# ProProject_new1_2024-06-04.net
KiCad netlist of a schematic drawn in EasyEDA Pro
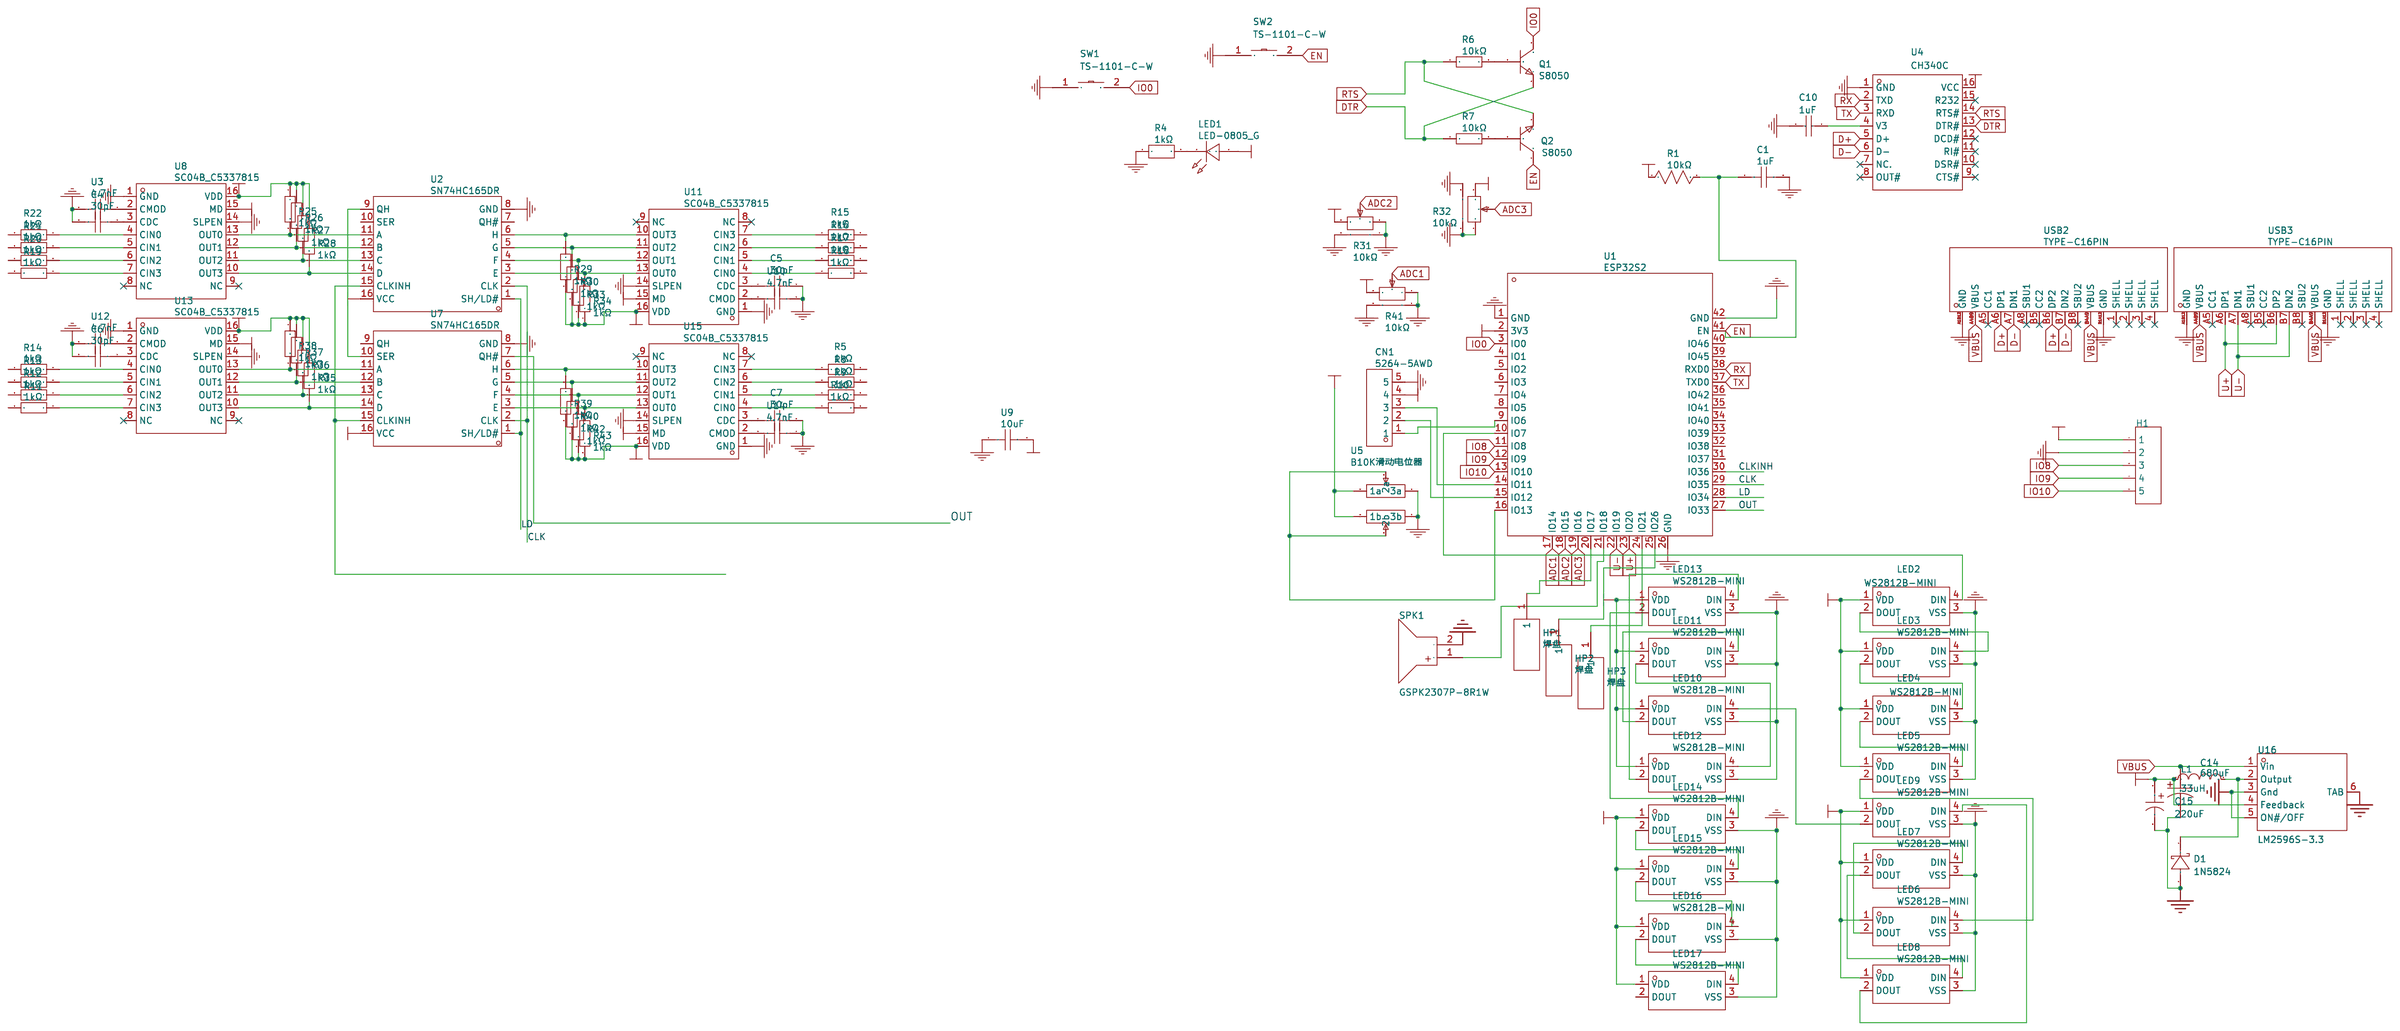
[diagram p0: schematic sheet]

(export (version "E")
  (design (tool "Eeschema 10.0.6"))
  (components
    (comp (ref "C1")
      (value "1uF")
      (footprint "easyedapro:C0603")
      (fields
        (field (name "Manufacturer Part") "CL10A105KB8NNNC")
        (field (name "Manufacturer") "SAMSUNG(三星)")
      )
      (libsource (lib "easyedapro") (part "1u"))
    )
    (comp (ref "C4")
      (value "30pF")
      (footprint "easyedapro:C0603")
      (fields
        (field (name "Manufacturer Part") "TCC0603COG300J500CT")
        (field (name "Manufacturer") "CCTC(三环)")
      )
      (libsource (lib "easyedapro") (part "30pF"))
    )
    (comp (ref "C5")
      (value "30pF")
      (footprint "easyedapro:C0603")
      (fields
        (field (name "Manufacturer Part") "TCC0603COG300J500CT")
        (field (name "Manufacturer") "CCTC(三环)")
      )
      (libsource (lib "easyedapro") (part "30pF"))
    )
    (comp (ref "C6")
      (value "30pF")
      (footprint "easyedapro:C0603")
      (fields
        (field (name "Manufacturer Part") "TCC0603COG300J500CT")
        (field (name "Manufacturer") "CCTC(三环)")
      )
      (libsource (lib "easyedapro") (part "30pF"))
    )
    (comp (ref "C7")
      (value "30pF")
      (footprint "easyedapro:C0603")
      (fields
        (field (name "Manufacturer Part") "TCC0603COG300J500CT")
        (field (name "Manufacturer") "CCTC(三环)")
      )
      (libsource (lib "easyedapro") (part "30pF"))
    )
    (comp (ref "C10")
      (value "1uF")
      (footprint "easyedapro:C0805")
      (fields
        (field (name "Manufacturer Part") "GRM21BR61E226ME44L")
        (field (name "Manufacturer") "muRata(村田)")
      )
      (libsource (lib "easyedapro") (part "1uF"))
    )
    (comp (ref "C14")
      (value "680uF")
      (footprint "easyedapro:CAP-TH_BD6.3-P2.50-D1.0-FD")
      (description "容值:680uF;精度:±20%;额定电压:10V;纹波电流:980mA@100kHz;等效串联电阻:50mΩ@300kHz;")
      (fields
        (field (name "Manufacturer Part") "SHW680UF10V6.3X11")
        (field (name "Manufacturer") "KNSCHA(科尼盛)")
      )
      (libsource (lib "easyedapro") (part "SHW680UF10V6.3X11"))
    )
    (comp (ref "C15")
      (value "220uF")
      (footprint "easyedapro:CAP-TH_BD8.0-P3.50-D0.6-FD-2")
      (description "容值:220uF;精度:±20%;额定电压:35V;纹波电流:1.7A@100kHz;等效串联电阻:40mΩ@100kHz;")
      (fields
        (field (name "Manufacturer Part") "KNH2220UF35V149EC0049")
        (field (name "Manufacturer") "KNSCHA(科尼盛)")
      )
      (libsource (lib "easyedapro") (part "KNH2220UF35V149EC0049"))
    )
    (comp (ref "CN1")
      (value "5264-5AWD")
      (footprint "easyedapro:CONN-TH_5P-P2.50_5264-5AWD")
      (fields (field (name "Manufacturer Part") "5264-5AWD米色") (field (name "Manufacturer") "BOOMELE(博穆精密)"))
      (libsource (lib "easyedapro") (part "5264-5AWD"))
    )
    (comp (ref "D1")
      (value "1N5824")
      (footprint "easyedapro:DO-27_BD5.3-L8.4-P12.40-D1.3-RD")
      (description "二极管配置:独立式;正向压降(Vf):550mV@5A;直流反向耐压(Vr):30V;平均整流电流(Io):5A;")
      (fields (field (name "Manufacturer") "FUXINSEMI(富芯森美)"))
      (libsource (lib "easyedapro") (part "1N5824_C7503125"))
    )
    (comp (ref "H1")
      (value "~")
      (footprint "easyedapro:HDR-TH_5P-P2.54-V-F")
      (libsource (lib "easyedapro") (part "Header-Female-2.54_1x5"))
    )
    (comp (ref "HP1")
      (value "焊盘")
      (footprint "easyedapro:焊盘")
      (fields (field (name "Manufacturer Part") "....."))
      (libsource (lib "easyedapro") (part "焊盘"))
    )
    (comp (ref "HP2")
      (value "焊盘")
      (footprint "easyedapro:焊盘")
      (fields (field (name "Manufacturer Part") "....."))
      (libsource (lib "easyedapro") (part "焊盘"))
    )
    (comp (ref "HP3")
      (value "焊盘")
      (footprint "easyedapro:焊盘")
      (fields (field (name "Manufacturer Part") "....."))
      (libsource (lib "easyedapro") (part "焊盘"))
    )
    (comp (ref "L1")
      (value "33uH")
      (footprint "easyedapro:IND-SMD_L7.0-W6.6_FXL0630")
      (description "电感值:33uH;精度:±20%;额定电流:2A;饱和电流(Isat):2.5A;类型:一体成型电感;")
      (fields (field (name "Manufacturer Part") "FXL0630-330-M") (field (name "Manufacturer") "cjiang(长江微电)"))
      (libsource (lib "easyedapro") (part "FXL0630-330-M"))
    )
    (comp (ref "LED1")
      (value "LED-0805_G")
      (footprint "easyedapro:LED0805_GREEN")
      (fields (field (name "Manufacturer Part") "NCD0805G1") (field (name "Manufacturer") "国星光电"))
      (libsource (lib "easyedapro") (part "LED-0805_G"))
    )
    (comp (ref "LED2")
      (value "WS2812B-MINI")
      (footprint "easyedapro:LED-SMD_4P-L3.5-W3.5-TL_WS2812B")
      (fields
        (field (name "Manufacturer Part") "WS2812B-MINI-V3/W")
        (field (name "Manufacturer") "worldsemi")
      )
      (libsource (lib "easyedapro") (part "WS2812B-MINI"))
    )
    (comp (ref "LED3")
      (value "WS2812B-MINI")
      (footprint "easyedapro:LED-SMD_4P-L3.5-W3.5-TL_WS2812B")
      (fields
        (field (name "Manufacturer Part") "WS2812B-MINI-V3/W")
        (field (name "Manufacturer") "worldsemi")
      )
      (libsource (lib "easyedapro") (part "WS2812B-MINI"))
    )
    (comp (ref "LED4")
      (value "WS2812B-MINI")
      (footprint "easyedapro:LED-SMD_4P-L3.5-W3.5-TL_WS2812B")
      (fields
        (field (name "Manufacturer Part") "WS2812B-MINI-V3/W")
        (field (name "Manufacturer") "worldsemi")
      )
      (libsource (lib "easyedapro") (part "WS2812B-MINI"))
    )
    (comp (ref "LED5")
      (value "WS2812B-MINI")
      (footprint "easyedapro:LED-SMD_4P-L3.5-W3.5-TL_WS2812B")
      (fields
        (field (name "Manufacturer Part") "WS2812B-MINI-V3/W")
        (field (name "Manufacturer") "worldsemi")
      )
      (libsource (lib "easyedapro") (part "WS2812B-MINI"))
    )
    (comp (ref "LED6")
      (value "WS2812B-MINI")
      (footprint "easyedapro:LED-SMD_4P-L3.5-W3.5-TL_WS2812B")
      (fields
        (field (name "Manufacturer Part") "WS2812B-MINI-V3/W")
        (field (name "Manufacturer") "worldsemi")
      )
      (libsource (lib "easyedapro") (part "WS2812B-MINI"))
    )
    (comp (ref "LED7")
      (value "WS2812B-MINI")
      (footprint "easyedapro:LED-SMD_4P-L3.5-W3.5-TL_WS2812B")
      (fields
        (field (name "Manufacturer Part") "WS2812B-MINI-V3/W")
        (field (name "Manufacturer") "worldsemi")
      )
      (libsource (lib "easyedapro") (part "WS2812B-MINI"))
    )
    (comp (ref "LED8")
      (value "WS2812B-MINI")
      (footprint "easyedapro:LED-SMD_4P-L3.5-W3.5-TL_WS2812B")
      (fields
        (field (name "Manufacturer Part") "WS2812B-MINI-V3/W")
        (field (name "Manufacturer") "worldsemi")
      )
      (libsource (lib "easyedapro") (part "WS2812B-MINI"))
    )
    (comp (ref "LED9")
      (value "WS2812B-MINI")
      (footprint "easyedapro:LED-SMD_4P-L3.5-W3.5-TL_WS2812B")
      (fields
        (field (name "Manufacturer Part") "WS2812B-MINI-V3/W")
        (field (name "Manufacturer") "worldsemi")
      )
      (libsource (lib "easyedapro") (part "WS2812B-MINI"))
    )
    (comp (ref "LED10")
      (value "WS2812B-MINI")
      (footprint "easyedapro:LED-SMD_4P-L3.5-W3.5-TL_WS2812B")
      (fields
        (field (name "Manufacturer Part") "WS2812B-MINI-V3/W")
        (field (name "Manufacturer") "worldsemi")
      )
      (libsource (lib "easyedapro") (part "WS2812B-MINI"))
    )
    (comp (ref "LED11")
      (value "WS2812B-MINI")
      (footprint "easyedapro:LED-SMD_4P-L3.5-W3.5-TL_WS2812B")
      (fields
        (field (name "Manufacturer Part") "WS2812B-MINI-V3/W")
        (field (name "Manufacturer") "worldsemi")
      )
      (libsource (lib "easyedapro") (part "WS2812B-MINI"))
    )
    (comp (ref "LED12")
      (value "WS2812B-MINI")
      (footprint "easyedapro:LED-SMD_4P-L3.5-W3.5-TL_WS2812B")
      (fields
        (field (name "Manufacturer Part") "WS2812B-MINI-V3/W")
        (field (name "Manufacturer") "worldsemi")
      )
      (libsource (lib "easyedapro") (part "WS2812B-MINI"))
    )
    (comp (ref "LED13")
      (value "WS2812B-MINI")
      (footprint "easyedapro:LED-SMD_4P-L3.5-W3.5-TL_WS2812B")
      (fields
        (field (name "Manufacturer Part") "WS2812B-MINI-V3/W")
        (field (name "Manufacturer") "worldsemi")
      )
      (libsource (lib "easyedapro") (part "WS2812B-MINI"))
    )
    (comp (ref "LED14")
      (value "WS2812B-MINI")
      (footprint "easyedapro:LED-SMD_4P-L3.5-W3.5-TL_WS2812B")
      (fields
        (field (name "Manufacturer Part") "WS2812B-MINI-V3/W")
        (field (name "Manufacturer") "worldsemi")
      )
      (libsource (lib "easyedapro") (part "WS2812B-MINI"))
    )
    (comp (ref "LED15")
      (value "WS2812B-MINI")
      (footprint "easyedapro:LED-SMD_4P-L3.5-W3.5-TL_WS2812B")
      (fields
        (field (name "Manufacturer Part") "WS2812B-MINI-V3/W")
        (field (name "Manufacturer") "worldsemi")
      )
      (libsource (lib "easyedapro") (part "WS2812B-MINI"))
    )
    (comp (ref "LED16")
      (value "WS2812B-MINI")
      (footprint "easyedapro:LED-SMD_4P-L3.5-W3.5-TL_WS2812B")
      (fields
        (field (name "Manufacturer Part") "WS2812B-MINI-V3/W")
        (field (name "Manufacturer") "worldsemi")
      )
      (libsource (lib "easyedapro") (part "WS2812B-MINI"))
    )
    (comp (ref "LED17")
      (value "WS2812B-MINI")
      (footprint "easyedapro:LED-SMD_4P-L3.5-W3.5-TL_WS2812B")
      (fields
        (field (name "Manufacturer Part") "WS2812B-MINI-V3/W")
        (field (name "Manufacturer") "worldsemi")
      )
      (libsource (lib "easyedapro") (part "WS2812B-MINI"))
    )
    (comp (ref "Q1")
      (value "S8050")
      (footprint "easyedapro:SOT-23-3_L2.9-W1.3-P1.90-LS2.4-BR")
      (fields (field (name "Manufacturer") "Yenji"))
      (libsource (lib "easyedapro") (part "S8050"))
    )
    (comp (ref "Q2")
      (value "S8050")
      (footprint "easyedapro:SOT-23-3_L2.9-W1.3-P1.90-LS2.4-BR")
      (fields (field (name "Manufacturer") "Yenji"))
      (libsource (lib "") (part "S8050_1"))
    )
    (comp (ref "R1")
      (value "10kΩ")
      (footprint "easyedapro:R0603")
      (fields
        (field (name "Manufacturer Part") "0603WAF1002T5E")
        (field (name "Manufacturer") "UNI-ROYAL(厚声)")
      )
      (libsource (lib "easyedapro") (part "10k"))
    )
    (comp (ref "R4")
      (value "1kΩ")
      (footprint "easyedapro:R0805")
      (fields
        (field (name "Manufacturer Part") "0805W8D1001T5E")
        (field (name "Manufacturer") "UNI-ROYAL(厚声)")
      )
      (libsource (lib "easyedapro") (part "1kΩ"))
    )
    (comp (ref "R5")
      (value "1kΩ")
      (footprint "easyedapro:R0603")
      (fields (field (name "Manufacturer Part") "ERJ3RBD1001V") (field (name "Manufacturer") "PANASONIC(松下)"))
      (libsource (lib "") (part "1kΩ_1"))
    )
    (comp (ref "R6")
      (value "10kΩ")
      (footprint "easyedapro:R0805")
      (fields
        (field (name "Manufacturer Part") "0805W8F1002T5E")
        (field (name "Manufacturer") "UNI-ROYAL(厚声)")
      )
      (libsource (lib "") (part "10kΩ_1"))
    )
    (comp (ref "R7")
      (value "10kΩ")
      (footprint "easyedapro:R0805")
      (fields
        (field (name "Manufacturer Part") "0805W8F1002T5E")
        (field (name "Manufacturer") "UNI-ROYAL(厚声)")
      )
      (libsource (lib "") (part "10kΩ_1"))
    )
    (comp (ref "R8")
      (value "1kΩ")
      (footprint "easyedapro:R0603")
      (fields (field (name "Manufacturer Part") "ERJ3RBD1001V") (field (name "Manufacturer") "PANASONIC(松下)"))
      (libsource (lib "") (part "1kΩ_1"))
    )
    (comp (ref "R9")
      (value "1kΩ")
      (footprint "easyedapro:R0603")
      (fields (field (name "Manufacturer Part") "ERJ3RBD1001V") (field (name "Manufacturer") "PANASONIC(松下)"))
      (libsource (lib "") (part "1kΩ_1"))
    )
    (comp (ref "R10")
      (value "1kΩ")
      (footprint "easyedapro:R0603")
      (fields (field (name "Manufacturer Part") "ERJ3RBD1001V") (field (name "Manufacturer") "PANASONIC(松下)"))
      (libsource (lib "") (part "1kΩ_1"))
    )
    (comp (ref "R11")
      (value "1kΩ")
      (footprint "easyedapro:R0603")
      (fields (field (name "Manufacturer Part") "ERJ3RBD1001V") (field (name "Manufacturer") "PANASONIC(松下)"))
      (libsource (lib "") (part "1kΩ_1"))
    )
    (comp (ref "R12")
      (value "1kΩ")
      (footprint "easyedapro:R0603")
      (fields (field (name "Manufacturer Part") "ERJ3RBD1001V") (field (name "Manufacturer") "PANASONIC(松下)"))
      (libsource (lib "") (part "1kΩ_1"))
    )
    (comp (ref "R13")
      (value "1kΩ")
      (footprint "easyedapro:R0603")
      (fields (field (name "Manufacturer Part") "ERJ3RBD1001V") (field (name "Manufacturer") "PANASONIC(松下)"))
      (libsource (lib "") (part "1kΩ_1"))
    )
    (comp (ref "R14")
      (value "1kΩ")
      (footprint "easyedapro:R0603")
      (fields (field (name "Manufacturer Part") "ERJ3RBD1001V") (field (name "Manufacturer") "PANASONIC(松下)"))
      (libsource (lib "") (part "1kΩ_1"))
    )
    (comp (ref "R15")
      (value "1kΩ")
      (footprint "easyedapro:R0603")
      (fields (field (name "Manufacturer Part") "ERJ3RBD1001V") (field (name "Manufacturer") "PANASONIC(松下)"))
      (libsource (lib "") (part "1kΩ_1"))
    )
    (comp (ref "R16")
      (value "1kΩ")
      (footprint "easyedapro:R0603")
      (fields (field (name "Manufacturer Part") "ERJ3RBD1001V") (field (name "Manufacturer") "PANASONIC(松下)"))
      (libsource (lib "") (part "1kΩ_1"))
    )
    (comp (ref "R17")
      (value "1kΩ")
      (footprint "easyedapro:R0603")
      (fields (field (name "Manufacturer Part") "ERJ3RBD1001V") (field (name "Manufacturer") "PANASONIC(松下)"))
      (libsource (lib "") (part "1kΩ_1"))
    )
    (comp (ref "R18")
      (value "1kΩ")
      (footprint "easyedapro:R0603")
      (fields (field (name "Manufacturer Part") "ERJ3RBD1001V") (field (name "Manufacturer") "PANASONIC(松下)"))
      (libsource (lib "") (part "1kΩ_1"))
    )
    (comp (ref "R19")
      (value "1kΩ")
      (footprint "easyedapro:R0603")
      (fields (field (name "Manufacturer Part") "ERJ3RBD1001V") (field (name "Manufacturer") "PANASONIC(松下)"))
      (libsource (lib "") (part "1kΩ_1"))
    )
    (comp (ref "R20")
      (value "1kΩ")
      (footprint "easyedapro:R0603")
      (fields (field (name "Manufacturer Part") "ERJ3RBD1001V") (field (name "Manufacturer") "PANASONIC(松下)"))
      (libsource (lib "") (part "1kΩ_1"))
    )
    (comp (ref "R21")
      (value "1kΩ")
      (footprint "easyedapro:R0603")
      (fields (field (name "Manufacturer Part") "ERJ3RBD1001V") (field (name "Manufacturer") "PANASONIC(松下)"))
      (libsource (lib "") (part "1kΩ_1"))
    )
    (comp (ref "R22")
      (value "1kΩ")
      (footprint "easyedapro:R0603")
      (fields (field (name "Manufacturer Part") "ERJ3RBD1001V") (field (name "Manufacturer") "PANASONIC(松下)"))
      (libsource (lib "") (part "1kΩ_1"))
    )
    (comp (ref "R25")
      (value "1kΩ")
      (footprint "easyedapro:R0603")
      (fields (field (name "Manufacturer Part") "ERJ3RBD1001V") (field (name "Manufacturer") "PANASONIC(松下)"))
      (libsource (lib "") (part "1kΩ_1"))
    )
    (comp (ref "R26")
      (value "1kΩ")
      (footprint "easyedapro:R0603")
      (fields (field (name "Manufacturer Part") "ERJ3RBD1001V") (field (name "Manufacturer") "PANASONIC(松下)"))
      (libsource (lib "") (part "1kΩ_1"))
    )
    (comp (ref "R27")
      (value "1kΩ")
      (footprint "easyedapro:R0603")
      (fields (field (name "Manufacturer Part") "ERJ3RBD1001V") (field (name "Manufacturer") "PANASONIC(松下)"))
      (libsource (lib "") (part "1kΩ_1"))
    )
    (comp (ref "R28")
      (value "1kΩ")
      (footprint "easyedapro:R0603")
      (fields (field (name "Manufacturer Part") "ERJ3RBD1001V") (field (name "Manufacturer") "PANASONIC(松下)"))
      (libsource (lib "") (part "1kΩ_1"))
    )
    (comp (ref "R29")
      (value "1kΩ")
      (footprint "easyedapro:R0603")
      (fields (field (name "Manufacturer Part") "ERJ3RBD1001V") (field (name "Manufacturer") "PANASONIC(松下)"))
      (libsource (lib "") (part "1kΩ_1"))
    )
    (comp (ref "R30")
      (value "1kΩ")
      (footprint "easyedapro:R0603")
      (fields (field (name "Manufacturer Part") "ERJ3RBD1001V") (field (name "Manufacturer") "PANASONIC(松下)"))
      (libsource (lib "") (part "1kΩ_1"))
    )
    (comp (ref "R31")
      (value "10kΩ")
      (footprint "easyedapro:RES-ADJ-TH_RK09K1130AJ3")
      (fields
        (field (name "Manufacturer Part") "RK09K1130AP5")
        (field (name "Manufacturer") "ALPSALPINE(阿尔卑斯阿尔派)")
      )
      (libsource (lib "easyedapro") (part "10kΩ"))
    )
    (comp (ref "R32")
      (value "10kΩ")
      (footprint "easyedapro:RES-ADJ-TH_RK09K1130AJ3")
      (fields
        (field (name "Manufacturer Part") "RK09K1130AP5")
        (field (name "Manufacturer") "ALPSALPINE(阿尔卑斯阿尔派)")
      )
      (libsource (lib "easyedapro") (part "10kΩ"))
    )
    (comp (ref "R33")
      (value "1kΩ")
      (footprint "easyedapro:R0603")
      (fields (field (name "Manufacturer Part") "ERJ3RBD1001V") (field (name "Manufacturer") "PANASONIC(松下)"))
      (libsource (lib "") (part "1kΩ_1"))
    )
    (comp (ref "R34")
      (value "1kΩ")
      (footprint "easyedapro:R0603")
      (fields (field (name "Manufacturer Part") "ERJ3RBD1001V") (field (name "Manufacturer") "PANASONIC(松下)"))
      (libsource (lib "") (part "1kΩ_1"))
    )
    (comp (ref "R35")
      (value "1kΩ")
      (footprint "easyedapro:R0603")
      (fields (field (name "Manufacturer Part") "ERJ3RBD1001V") (field (name "Manufacturer") "PANASONIC(松下)"))
      (libsource (lib "") (part "1kΩ_1"))
    )
    (comp (ref "R36")
      (value "1kΩ")
      (footprint "easyedapro:R0603")
      (fields (field (name "Manufacturer Part") "ERJ3RBD1001V") (field (name "Manufacturer") "PANASONIC(松下)"))
      (libsource (lib "") (part "1kΩ_1"))
    )
    (comp (ref "R37")
      (value "1kΩ")
      (footprint "easyedapro:R0603")
      (fields (field (name "Manufacturer Part") "ERJ3RBD1001V") (field (name "Manufacturer") "PANASONIC(松下)"))
      (libsource (lib "") (part "1kΩ_1"))
    )
    (comp (ref "R38")
      (value "1kΩ")
      (footprint "easyedapro:R0603")
      (fields (field (name "Manufacturer Part") "ERJ3RBD1001V") (field (name "Manufacturer") "PANASONIC(松下)"))
      (libsource (lib "") (part "1kΩ_1"))
    )
    (comp (ref "R39")
      (value "1kΩ")
      (footprint "easyedapro:R0603")
      (fields (field (name "Manufacturer Part") "ERJ3RBD1001V") (field (name "Manufacturer") "PANASONIC(松下)"))
      (libsource (lib "") (part "1kΩ_1"))
    )
    (comp (ref "R40")
      (value "1kΩ")
      (footprint "easyedapro:R0603")
      (fields (field (name "Manufacturer Part") "ERJ3RBD1001V") (field (name "Manufacturer") "PANASONIC(松下)"))
      (libsource (lib "") (part "1kΩ_1"))
    )
    (comp (ref "R41")
      (value "10kΩ")
      (footprint "easyedapro:RES-ADJ-TH_RK09K1130AJ3")
      (fields
        (field (name "Manufacturer Part") "RK09K1130AP5")
        (field (name "Manufacturer") "ALPSALPINE(阿尔卑斯阿尔派)")
      )
      (libsource (lib "easyedapro") (part "10kΩ"))
    )
    (comp (ref "R42")
      (value "1kΩ")
      (footprint "easyedapro:R0603")
      (fields (field (name "Manufacturer Part") "ERJ3RBD1001V") (field (name "Manufacturer") "PANASONIC(松下)"))
      (libsource (lib "") (part "1kΩ_1"))
    )
    (comp (ref "R43")
      (value "1kΩ")
      (footprint "easyedapro:R0603")
      (fields (field (name "Manufacturer Part") "ERJ3RBD1001V") (field (name "Manufacturer") "PANASONIC(松下)"))
      (libsource (lib "") (part "1kΩ_1"))
    )
    (comp (ref "SPK1")
      (value "GSPK2307P-8R1W")
      (footprint "easyedapro:SPK-TH_BD23.0-P10.00-D0.8-L-RD")
      (fields (field (name "Manufacturer") "INGHAi(赢海)"))
      (libsource (lib "easyedapro") (part "GSPK2307P-8R1W"))
    )
    (comp (ref "SW1")
      (value "TS-1101-C-W")
      (footprint "easyedapro:SW-SMD_L6.0-W3.3-LS8.0")
      (fields (field (name "Manufacturer") "XKB Connectivity(中国星坤)"))
      (libsource (lib "easyedapro") (part "TS-1101-C-W"))
    )
    (comp (ref "SW2")
      (value "TS-1101-C-W")
      (footprint "easyedapro:SW-SMD_L6.0-W3.3-LS8.0")
      (fields (field (name "Manufacturer") "XKB Connectivity(中国星坤)"))
      (libsource (lib "easyedapro") (part "TS-1101-C-W"))
    )
    (comp (ref "U1")
      (value "ESP32S2")
      (footprint "easyedapro:ESP32S2")
      (fields
        (field (name "Manufacturer Part") "ESP32-S2-WROVER-I-N8R2")
        (field (name "Manufacturer") "ESPRESSIF(乐鑫)")
      )
      (libsource (lib "easyedapro") (part "ESP32S2"))
    )
    (comp (ref "U2")
      (value "SN74HC165DR")
      (footprint "easyedapro:SOP-16_L10.0-W3.9-P1.27-LS6.0-BL")
      (fields (field (name "Manufacturer") "TI(德州仪器)"))
      (libsource (lib "easyedapro") (part "SN74HC165DR"))
    )
    (comp (ref "U3")
      (value "4.7nF")
      (footprint "easyedapro:C0603")
      (fields (field (name "Manufacturer Part") "C1608JB2A472M080AA") (field (name "Manufacturer") "TDK"))
      (libsource (lib "easyedapro") (part "4.7nF"))
    )
    (comp (ref "U4")
      (value "CH340C")
      (footprint "easyedapro:SOP-16_L10.0-W3.9-P1.27-LS6.0-BL")
      (fields (field (name "Manufacturer") "WCH(南京沁恒)"))
      (libsource (lib "easyedapro") (part "CH340C"))
    )
    (comp (ref "U5")
      (value "B10K滑动电位器")
      (footprint "easyedapro:B10K")
      (libsource (lib "easyedapro") (part "B10K滑动电位器"))
    )
    (comp (ref "U7")
      (value "SN74HC165DR")
      (footprint "easyedapro:SOP-16_L10.0-W3.9-P1.27-LS6.0-BL")
      (fields (field (name "Manufacturer") "TI(德州仪器)"))
      (libsource (lib "easyedapro") (part "SN74HC165DR"))
    )
    (comp (ref "U8")
      (value "SC04B_C5337815")
      (footprint "easyedapro:SOP-16_L10.0-W3.9-P1.27-LS6.0-BL")
      (fields (field (name "Manufacturer Part") "SC04B") (field (name "Manufacturer") "icman(晶尊微)"))
      (libsource (lib "easyedapro") (part "SC04B_C5337815"))
    )
    (comp (ref "U9")
      (value "10uF")
      (footprint "easyedapro:C1206")
      (fields
        (field (name "Manufacturer Part") "CS3216Y5V106Z350NRI")
        (field (name "Manufacturer") "SAMWHA(三和)")
      )
      (libsource (lib "easyedapro") (part "10uF"))
    )
    (comp (ref "U10")
      (value "4.7nF")
      (footprint "easyedapro:C0603")
      (fields (field (name "Manufacturer Part") "C1608JB2A472M080AA") (field (name "Manufacturer") "TDK"))
      (libsource (lib "easyedapro") (part "4.7nF"))
    )
    (comp (ref "U11")
      (value "SC04B_C5337815")
      (footprint "easyedapro:SOP-16_L10.0-W3.9-P1.27-LS6.0-BL")
      (fields (field (name "Manufacturer Part") "SC04B") (field (name "Manufacturer") "icman(晶尊微)"))
      (libsource (lib "easyedapro") (part "SC04B_C5337815"))
    )
    (comp (ref "U12")
      (value "4.7nF")
      (footprint "easyedapro:C0603")
      (fields (field (name "Manufacturer Part") "C1608JB2A472M080AA") (field (name "Manufacturer") "TDK"))
      (libsource (lib "easyedapro") (part "4.7nF"))
    )
    (comp (ref "U13")
      (value "SC04B_C5337815")
      (footprint "easyedapro:SOP-16_L10.0-W3.9-P1.27-LS6.0-BL")
      (fields (field (name "Manufacturer Part") "SC04B") (field (name "Manufacturer") "icman(晶尊微)"))
      (libsource (lib "easyedapro") (part "SC04B_C5337815"))
    )
    (comp (ref "U14")
      (value "4.7nF")
      (footprint "easyedapro:C0603")
      (fields (field (name "Manufacturer Part") "C1608JB2A472M080AA") (field (name "Manufacturer") "TDK"))
      (libsource (lib "easyedapro") (part "4.7nF"))
    )
    (comp (ref "U15")
      (value "SC04B_C5337815")
      (footprint "easyedapro:SOP-16_L10.0-W3.9-P1.27-LS6.0-BL")
      (fields (field (name "Manufacturer Part") "SC04B") (field (name "Manufacturer") "icman(晶尊微)"))
      (libsource (lib "easyedapro") (part "SC04B_C5337815"))
    )
    (comp (ref "U16")
      (value "LM2596S-3.3")
      (footprint "easyedapro:TO-263-5_L10.0-W8.4-P1.70-LS15.3-BR")
      (description "功能类型:降压型;输出类型:固定;输入电压:40V;输出电压:3.3V;输出电流(最大值):3A;")
      (fields (field (name "Manufacturer") "UMW(友台半导体)"))
      (libsource (lib "easyedapro") (part "LM2596S-3.3"))
    )
    (comp (ref "USB2")
      (value "TYPE-C16PIN")
      (footprint "easyedapro:USB-C-SMD_TYPE-C16PIN")
      (fields (field (name "Manufacturer") "SHOU HAN(首韩)"))
      (libsource (lib "easyedapro") (part "TYPE-C16PIN"))
    )
    (comp (ref "USB3")
      (value "TYPE-C16PIN")
      (footprint "easyedapro:USB-C-SMD_TYPE-C16PIN")
      (fields (field (name "Manufacturer") "SHOU HAN(首韩)"))
      (libsource (lib "easyedapro") (part "TYPE-C16PIN"))
    )
  )
  (nets
    (net (code "1") (name "/CLK") (class "Default")
      (node (ref "U1") (pin "29") (pinfunction "IO35_29") (pintype "unspecified"))
      (node (ref "U2") (pin "2") (pinfunction "CLK_2") (pintype "unspecified"))
      (node (ref "U7") (pin "2") (pinfunction "CLK_2") (pintype "unspecified"))
    )
    (net (code "2") (name "/CLKINH") (class "Default")
      (node (ref "U1") (pin "30") (pinfunction "IO36_30") (pintype "unspecified"))
    )
    (net (code "3") (name "/LD") (class "Default")
      (node (ref "U1") (pin "28") (pinfunction "IO34_28") (pintype "unspecified"))
      (node (ref "U2") (pin "1") (pinfunction "SH/LD#_1") (pintype "unspecified"))
      (node (ref "U7") (pin "1") (pinfunction "SH/LD#_1") (pintype "unspecified"))
    )
    (net (code "4") (name "/OUT") (class "Default")
      (node (ref "U1") (pin "27") (pinfunction "IO33_27") (pintype "unspecified"))
      (node (ref "U7") (pin "7") (pinfunction "QH#_7") (pintype "unspecified"))
    )
    (net (code "5") (name "ADC1") (class "Default")
      (node (ref "R41") (pin "2") (pinfunction "2_2") (pintype "input"))
      (node (ref "U1") (pin "17") (pinfunction "IO14_17") (pintype "unspecified"))
    )
    (net (code "6") (name "ADC2") (class "Default")
      (node (ref "R31") (pin "2") (pinfunction "2_2") (pintype "input"))
      (node (ref "U1") (pin "18") (pinfunction "IO15_18") (pintype "unspecified"))
    )
    (net (code "7") (name "ADC3") (class "Default")
      (node (ref "R32") (pin "2") (pinfunction "2_2") (pintype "input"))
      (node (ref "U1") (pin "19") (pinfunction "IO16_19") (pintype "unspecified"))
    )
    (net (code "8") (name "D+") (class "Default")
      (node (ref "U4") (pin "5") (pinfunction "D+_5") (pintype "unspecified"))
      (node (ref "USB2") (pin "A6") (pinfunction "DP1_A6") (pintype "unspecified"))
      (node (ref "USB2") (pin "B6") (pinfunction "DP2_B6") (pintype "unspecified"))
    )
    (net (code "9") (name "D-") (class "Default")
      (node (ref "U4") (pin "6") (pinfunction "D-_6") (pintype "unspecified"))
      (node (ref "USB2") (pin "A7") (pinfunction "DN1_A7") (pintype "unspecified"))
      (node (ref "USB2") (pin "B7") (pinfunction "DN2_B7") (pintype "unspecified"))
    )
    (net (code "10") (name "DTR") (class "Default")
      (node (ref "Q1") (pin "2") (pinfunction "E_2") (pintype "unspecified"))
      (node (ref "R7") (pin "1") (pinfunction "1_1") (pintype "input"))
      (node (ref "U4") (pin "13") (pinfunction "DTR#_13") (pintype "unspecified"))
    )
    (net (code "11") (name "EN") (class "Default")
      (node (ref "C1") (pin "1") (pinfunction "1_1") (pintype "unspecified"))
      (node (ref "Q2") (pin "3") (pinfunction "C_3") (pintype "unspecified"))
      (node (ref "R1") (pin "2") (pinfunction "2_2") (pintype "unspecified"))
      (node (ref "SW2") (pin "2") (pinfunction "2_2") (pintype "unspecified"))
      (node (ref "U1") (pin "41") (pinfunction "EN_41") (pintype "unspecified"))
    )
    (net (code "12") (name "GND") (class "Default")
      (node (ref "C1") (pin "2") (pinfunction "2_2") (pintype "unspecified"))
      (node (ref "C10") (pin "2") (pinfunction "2_2") (pintype "input"))
      (node (ref "C14") (pin "2") (pinfunction "2_2") (pintype "unspecified"))
      (node (ref "C15") (pin "2") (pinfunction "2_2") (pintype "input"))
      (node (ref "C4") (pin "2") (pinfunction "2_2") (pintype "unspecified"))
      (node (ref "C5") (pin "2") (pinfunction "2_2") (pintype "unspecified"))
      (node (ref "C6") (pin "2") (pinfunction "2_2") (pintype "unspecified"))
      (node (ref "C7") (pin "2") (pinfunction "2_2") (pintype "unspecified"))
      (node (ref "CN1") (pin "5") (pinfunction "5_5") (pintype "unspecified"))
      (node (ref "D1") (pin "2") (pinfunction "A_2") (pintype "unspecified"))
      (node (ref "H1") (pin "2") (pinfunction "2_2") (pintype "input"))
      (node (ref "LED10") (pin "3") (pinfunction "VSS_3") (pintype "unspecified"))
      (node (ref "LED11") (pin "3") (pinfunction "VSS_3") (pintype "unspecified"))
      (node (ref "LED12") (pin "3") (pinfunction "VSS_3") (pintype "unspecified"))
      (node (ref "LED13") (pin "3") (pinfunction "VSS_3") (pintype "unspecified"))
      (node (ref "LED14") (pin "3") (pinfunction "VSS_3") (pintype "unspecified"))
      (node (ref "LED15") (pin "3") (pinfunction "VSS_3") (pintype "unspecified"))
      (node (ref "LED16") (pin "3") (pinfunction "VSS_3") (pintype "unspecified"))
      (node (ref "LED17") (pin "3") (pinfunction "VSS_3") (pintype "unspecified"))
      (node (ref "LED2") (pin "3") (pinfunction "VSS_3") (pintype "unspecified"))
      (node (ref "LED3") (pin "3") (pinfunction "VSS_3") (pintype "unspecified"))
      (node (ref "LED4") (pin "3") (pinfunction "VSS_3") (pintype "unspecified"))
      (node (ref "LED5") (pin "3") (pinfunction "VSS_3") (pintype "unspecified"))
      (node (ref "LED6") (pin "3") (pinfunction "VSS_3") (pintype "unspecified"))
      (node (ref "LED7") (pin "3") (pinfunction "VSS_3") (pintype "unspecified"))
      (node (ref "LED8") (pin "3") (pinfunction "VSS_3") (pintype "unspecified"))
      (node (ref "LED9") (pin "3") (pinfunction "VSS_3") (pintype "unspecified"))
      (node (ref "R31") (pin "1") (pinfunction "1_1") (pintype "input"))
      (node (ref "R31") (pin "4") (pinfunction "4_4") (pintype "input"))
      (node (ref "R31") (pin "5") (pinfunction "5_5") (pintype "input"))
      (node (ref "R32") (pin "1") (pinfunction "1_1") (pintype "input"))
      (node (ref "R32") (pin "4") (pinfunction "4_4") (pintype "input"))
      (node (ref "R32") (pin "5") (pinfunction "5_5") (pintype "input"))
      (node (ref "R4") (pin "1") (pinfunction "1_1") (pintype "unspecified"))
      (node (ref "R41") (pin "1") (pinfunction "1_1") (pintype "input"))
      (node (ref "R41") (pin "4") (pinfunction "4_4") (pintype "input"))
      (node (ref "R41") (pin "5") (pinfunction "5_5") (pintype "input"))
      (node (ref "SPK1") (pin "2") (pinfunction "-_2") (pintype "input"))
      (node (ref "SW1") (pin "1") (pinfunction "1_1") (pintype "unspecified"))
      (node (ref "SW2") (pin "1") (pinfunction "1_1") (pintype "unspecified"))
      (node (ref "U1") (pin "1") (pinfunction "GND_1") (pintype "unspecified"))
      (node (ref "U1") (pin "26") (pinfunction "GND_26") (pintype "unspecified"))
      (node (ref "U1") (pin "42") (pinfunction "GND_42") (pintype "unspecified"))
      (node (ref "U10") (pin "1") (pinfunction "1_1") (pintype "unspecified"))
      (node (ref "U11") (pin "1") (pinfunction "GND_1") (pintype "unspecified"))
      (node (ref "U11") (pin "14") (pinfunction "SLPEN_14") (pintype "unspecified"))
      (node (ref "U12") (pin "1") (pinfunction "1_1") (pintype "unspecified"))
      (node (ref "U13") (pin "1") (pinfunction "GND_1") (pintype "unspecified"))
      (node (ref "U13") (pin "14") (pinfunction "SLPEN_14") (pintype "unspecified"))
      (node (ref "U14") (pin "1") (pinfunction "1_1") (pintype "unspecified"))
      (node (ref "U15") (pin "1") (pinfunction "GND_1") (pintype "unspecified"))
      (node (ref "U15") (pin "14") (pinfunction "SLPEN_14") (pintype "unspecified"))
      (node (ref "U16") (pin "3") (pinfunction "Gnd_3") (pintype "unspecified"))
      (node (ref "U16") (pin "5") (pinfunction "ON#/OFF_5") (pintype "unspecified"))
      (node (ref "U16") (pin "6") (pinfunction "TAB_6") (pintype "unspecified"))
      (node (ref "U2") (pin "8") (pinfunction "GND_8") (pintype "unspecified"))
      (node (ref "U3") (pin "1") (pinfunction "1_1") (pintype "unspecified"))
      (node (ref "U4") (pin "1") (pinfunction "GND_1") (pintype "unspecified"))
      (node (ref "U5") (pin "3a") (pinfunction "3a_3a") (pintype "unspecified"))
      (node (ref "U5") (pin "3b") (pinfunction "3b_3b") (pintype "unspecified"))
      (node (ref "U7") (pin "8") (pinfunction "GND_8") (pintype "unspecified"))
      (node (ref "U8") (pin "1") (pinfunction "GND_1") (pintype "unspecified"))
      (node (ref "U8") (pin "14") (pinfunction "SLPEN_14") (pintype "unspecified"))
      (node (ref "U9") (pin "1") (pinfunction "1_1") (pintype "unspecified"))
      (node (ref "USB2") (pin "A1B12") (pinfunction "GND_A1B12") (pintype "unspecified"))
      (node (ref "USB2") (pin "B1A12") (pinfunction "GND_B1A12") (pintype "unspecified"))
      (node (ref "USB3") (pin "A1B12") (pinfunction "GND_A1B12") (pintype "unspecified"))
      (node (ref "USB3") (pin "B1A12") (pinfunction "GND_B1A12") (pintype "unspecified"))
    )
    (net (code "13") (name "IO0") (class "Default")
      (node (ref "Q1") (pin "3") (pinfunction "C_3") (pintype "unspecified"))
      (node (ref "SW1") (pin "2") (pinfunction "2_2") (pintype "unspecified"))
      (node (ref "U1") (pin "3") (pinfunction "IO0_3") (pintype "unspecified"))
    )
    (net (code "14") (name "IO8") (class "Default")
      (node (ref "H1") (pin "3") (pinfunction "3_3") (pintype "input"))
      (node (ref "U1") (pin "11") (pinfunction "IO8_11") (pintype "unspecified"))
    )
    (net (code "15") (name "IO9") (class "Default")
      (node (ref "H1") (pin "4") (pinfunction "4_4") (pintype "input"))
      (node (ref "U1") (pin "12") (pinfunction "IO9_12") (pintype "unspecified"))
    )
    (net (code "16") (name "IO10") (class "Default")
      (node (ref "H1") (pin "5") (pinfunction "5_5") (pintype "input"))
      (node (ref "U1") (pin "13") (pinfunction "IO10_13") (pintype "unspecified"))
    )
    (net (code "17") (name "Net-(D1-K)") (class "Default")
      (node (ref "D1") (pin "1") (pinfunction "K_1") (pintype "unspecified"))
      (node (ref "L1") (pin "2") (pinfunction "2_2") (pintype "unspecified"))
      (node (ref "U16") (pin "2") (pinfunction "Output_2") (pintype "unspecified"))
    )
    (net (code "18") (name "Net-(LED1-Pad2)") (class "Default")
      (node (ref "LED1") (pin "2") (pinfunction "2_2") (pintype "unspecified"))
      (node (ref "R4") (pin "2") (pinfunction "2_2") (pintype "unspecified"))
    )
    (net (code "19") (name "Net-(LED2-DIN)") (class "Default")
      (node (ref "LED2") (pin "4") (pinfunction "DIN_4") (pintype "unspecified"))
      (node (ref "U1") (pin "10") (pinfunction "IO7_10") (pintype "unspecified"))
    )
    (net (code "20") (name "Net-(LED2-DOUT)") (class "Default")
      (node (ref "LED2") (pin "2") (pinfunction "DOUT_2") (pintype "unspecified"))
      (node (ref "LED3") (pin "4") (pinfunction "DIN_4") (pintype "unspecified"))
    )
    (net (code "21") (name "Net-(LED3-DOUT)") (class "Default")
      (node (ref "LED3") (pin "2") (pinfunction "DOUT_2") (pintype "unspecified"))
      (node (ref "LED4") (pin "4") (pinfunction "DIN_4") (pintype "unspecified"))
    )
    (net (code "22") (name "Net-(LED4-DOUT)") (class "Default")
      (node (ref "LED4") (pin "2") (pinfunction "DOUT_2") (pintype "unspecified"))
      (node (ref "LED5") (pin "4") (pinfunction "DIN_4") (pintype "unspecified"))
    )
    (net (code "23") (name "Net-(LED5-DOUT)") (class "Default")
      (node (ref "LED5") (pin "2") (pinfunction "DOUT_2") (pintype "unspecified"))
      (node (ref "LED6") (pin "4") (pinfunction "DIN_4") (pintype "unspecified"))
    )
    (net (code "24") (name "Net-(LED6-DOUT)") (class "Default")
      (node (ref "LED6") (pin "2") (pinfunction "DOUT_2") (pintype "unspecified"))
      (node (ref "LED7") (pin "4") (pinfunction "DIN_4") (pintype "unspecified"))
    )
    (net (code "25") (name "Net-(LED7-DOUT)") (class "Default")
      (node (ref "LED7") (pin "2") (pinfunction "DOUT_2") (pintype "unspecified"))
      (node (ref "LED8") (pin "4") (pinfunction "DIN_4") (pintype "unspecified"))
    )
    (net (code "26") (name "Net-(LED8-DOUT)") (class "Default")
      (node (ref "LED8") (pin "2") (pinfunction "DOUT_2") (pintype "unspecified"))
      (node (ref "LED9") (pin "4") (pinfunction "DIN_4") (pintype "unspecified"))
    )
    (net (code "27") (name "Net-(LED10-DIN)") (class "Default")
      (node (ref "LED10") (pin "4") (pinfunction "DIN_4") (pintype "unspecified"))
      (node (ref "LED9") (pin "2") (pinfunction "DOUT_2") (pintype "unspecified"))
    )
    (net (code "28") (name "Net-(LED10-DOUT)") (class "Default")
      (node (ref "LED10") (pin "2") (pinfunction "DOUT_2") (pintype "unspecified"))
      (node (ref "LED11") (pin "4") (pinfunction "DIN_4") (pintype "unspecified"))
    )
    (net (code "29") (name "Net-(LED11-DOUT)") (class "Default")
      (node (ref "LED11") (pin "2") (pinfunction "DOUT_2") (pintype "unspecified"))
      (node (ref "LED12") (pin "4") (pinfunction "DIN_4") (pintype "unspecified"))
    )
    (net (code "30") (name "Net-(LED12-DOUT)") (class "Default")
      (node (ref "LED12") (pin "2") (pinfunction "DOUT_2") (pintype "unspecified"))
      (node (ref "LED13") (pin "4") (pinfunction "DIN_4") (pintype "unspecified"))
    )
    (net (code "31") (name "Net-(LED13-DOUT)") (class "Default")
      (node (ref "LED13") (pin "2") (pinfunction "DOUT_2") (pintype "unspecified"))
      (node (ref "LED14") (pin "4") (pinfunction "DIN_4") (pintype "unspecified"))
    )
    (net (code "32") (name "Net-(LED14-DOUT)") (class "Default")
      (node (ref "LED14") (pin "2") (pinfunction "DOUT_2") (pintype "unspecified"))
      (node (ref "LED15") (pin "4") (pinfunction "DIN_4") (pintype "unspecified"))
    )
    (net (code "33") (name "Net-(LED15-DOUT)") (class "Default")
      (node (ref "LED15") (pin "2") (pinfunction "DOUT_2") (pintype "unspecified"))
      (node (ref "LED16") (pin "4") (pinfunction "DIN_4") (pintype "unspecified"))
    )
    (net (code "34") (name "Net-(LED16-DOUT)") (class "Default")
      (node (ref "LED16") (pin "2") (pinfunction "DOUT_2") (pintype "unspecified"))
      (node (ref "LED17") (pin "4") (pinfunction "DIN_4") (pintype "unspecified"))
    )
    (net (code "35") (name "Net-(Q1-B)") (class "Default")
      (node (ref "Q1") (pin "1") (pinfunction "B_1") (pintype "unspecified"))
      (node (ref "R6") (pin "2") (pinfunction "2_2") (pintype "input"))
    )
    (net (code "36") (name "Net-(Q2-B)") (class "Default")
      (node (ref "Q2") (pin "1") (pinfunction "B_1") (pintype "unspecified"))
      (node (ref "R7") (pin "2") (pinfunction "2_2") (pintype "input"))
    )
    (net (code "37") (name "Net-(SPK1-+)") (class "Default")
      (node (ref "SPK1") (pin "1") (pinfunction "+_1") (pintype "input"))
      (node (ref "U1") (pin "21") (pinfunction "IO18_21") (pintype "unspecified"))
    )
    (net (code "38") (name "Net-(U1-IO6)") (class "Default")
      (node (ref "CN1") (pin "1") (pinfunction "1_1") (pintype "unspecified"))
      (node (ref "U1") (pin "9") (pinfunction "IO6_9") (pintype "unspecified"))
    )
    (net (code "39") (name "Net-(U1-IO11)") (class "Default")
      (node (ref "CN1") (pin "3") (pinfunction "3_3") (pintype "unspecified"))
      (node (ref "U1") (pin "14") (pinfunction "IO11_14") (pintype "unspecified"))
    )
    (net (code "40") (name "Net-(U1-IO12)") (class "Default")
      (node (ref "CN1") (pin "2") (pinfunction "2_2") (pintype "unspecified"))
      (node (ref "U1") (pin "15") (pinfunction "IO12_15") (pintype "unspecified"))
    )
    (net (code "41") (name "Net-(U1-IO13)") (class "Default")
      (node (ref "U1") (pin "16") (pinfunction "IO13_16") (pintype "unspecified"))
      (node (ref "U5") (pin "2a") (pinfunction "2a_2a") (pintype "unspecified"))
      (node (ref "U5") (pin "2b") (pinfunction "2b_2b") (pintype "unspecified"))
    )
    (net (code "42") (name "Net-(U1-IO17)") (class "Default")
      (node (ref "HP1") (pin "1") (pinfunction "1_1") (pintype "bidirectional"))
      (node (ref "U1") (pin "20") (pinfunction "IO17_20") (pintype "unspecified"))
    )
    (net (code "43") (name "Net-(U1-IO21)") (class "Default")
      (node (ref "HP3") (pin "1") (pinfunction "1_1") (pintype "bidirectional"))
      (node (ref "U1") (pin "24") (pinfunction "IO21_24") (pintype "unspecified"))
    )
    (net (code "44") (name "Net-(U1-IO26)") (class "Default")
      (node (ref "HP2") (pin "1") (pinfunction "1_1") (pintype "bidirectional"))
      (node (ref "U1") (pin "25") (pinfunction "IO26_25") (pintype "unspecified"))
    )
    (net (code "45") (name "Net-(U2-A)") (class "Default")
      (node (ref "R25") (pin "2") (pinfunction "2_2") (pintype "unspecified"))
      (node (ref "U2") (pin "11") (pinfunction "A_11") (pintype "unspecified"))
      (node (ref "U8") (pin "13") (pinfunction "OUT0_13") (pintype "unspecified"))
    )
    (net (code "46") (name "Net-(U2-B)") (class "Default")
      (node (ref "R26") (pin "2") (pinfunction "2_2") (pintype "unspecified"))
      (node (ref "U2") (pin "12") (pinfunction "B_12") (pintype "unspecified"))
      (node (ref "U8") (pin "12") (pinfunction "OUT1_12") (pintype "unspecified"))
    )
    (net (code "47") (name "Net-(U2-C)") (class "Default")
      (node (ref "R27") (pin "2") (pinfunction "2_2") (pintype "unspecified"))
      (node (ref "U2") (pin "13") (pinfunction "C_13") (pintype "unspecified"))
      (node (ref "U8") (pin "11") (pinfunction "OUT2_11") (pintype "unspecified"))
    )
    (net (code "48") (name "Net-(U2-CLKINH)") (class "Default")
      (node (ref "U2") (pin "15") (pinfunction "CLKINH_15") (pintype "unspecified"))
      (node (ref "U7") (pin "15") (pinfunction "CLKINH_15") (pintype "unspecified"))
    )
    (net (code "49") (name "Net-(U2-D)") (class "Default")
      (node (ref "R28") (pin "2") (pinfunction "2_2") (pintype "unspecified"))
      (node (ref "U2") (pin "14") (pinfunction "D_14") (pintype "unspecified"))
      (node (ref "U8") (pin "10") (pinfunction "OUT3_10") (pintype "unspecified"))
    )
    (net (code "50") (name "Net-(U2-QH)") (class "Default")
      (node (ref "U2") (pin "9") (pinfunction "QH_9") (pintype "unspecified"))
      (node (ref "U7") (pin "10") (pinfunction "SER_10") (pintype "unspecified"))
    )
    (net (code "51") (name "Net-(U4-V3)") (class "Default")
      (node (ref "C10") (pin "1") (pinfunction "1_1") (pintype "input"))
      (node (ref "U4") (pin "4") (pinfunction "V3_4") (pintype "unspecified"))
    )
    (net (code "52") (name "Net-(U8-CDC)") (class "Default")
      (node (ref "C4") (pin "1") (pinfunction "1_1") (pintype "unspecified"))
      (node (ref "U8") (pin "3") (pinfunction "CDC_3") (pintype "unspecified"))
    )
    (net (code "53") (name "Net-(U8-CIN0)") (class "Default")
      (node (ref "R22") (pin "1") (pinfunction "1_1") (pintype "unspecified"))
      (node (ref "U8") (pin "4") (pinfunction "CIN0_4") (pintype "unspecified"))
    )
    (net (code "54") (name "Net-(U8-CIN1)") (class "Default")
      (node (ref "R21") (pin "1") (pinfunction "1_1") (pintype "unspecified"))
      (node (ref "U8") (pin "5") (pinfunction "CIN1_5") (pintype "unspecified"))
    )
    (net (code "55") (name "Net-(U8-CIN2)") (class "Default")
      (node (ref "R20") (pin "1") (pinfunction "1_1") (pintype "unspecified"))
      (node (ref "U8") (pin "6") (pinfunction "CIN2_6") (pintype "unspecified"))
    )
    (net (code "56") (name "Net-(U8-CIN3)") (class "Default")
      (node (ref "R19") (pin "1") (pinfunction "1_1") (pintype "unspecified"))
      (node (ref "U8") (pin "7") (pinfunction "CIN3_7") (pintype "unspecified"))
    )
    (net (code "57") (name "Net-(U8-CMOD)") (class "Default")
      (node (ref "U3") (pin "2") (pinfunction "2_2") (pintype "unspecified"))
      (node (ref "U8") (pin "2") (pinfunction "CMOD_2") (pintype "unspecified"))
    )
    (net (code "58") (name "Net-(U11-CDC)") (class "Default")
      (node (ref "C5") (pin "1") (pinfunction "1_1") (pintype "unspecified"))
      (node (ref "U11") (pin "3") (pinfunction "CDC_3") (pintype "unspecified"))
    )
    (net (code "59") (name "Net-(U11-CIN0)") (class "Default")
      (node (ref "R18") (pin "1") (pinfunction "1_1") (pintype "unspecified"))
      (node (ref "U11") (pin "4") (pinfunction "CIN0_4") (pintype "unspecified"))
    )
    (net (code "60") (name "Net-(U11-CIN1)") (class "Default")
      (node (ref "R17") (pin "1") (pinfunction "1_1") (pintype "unspecified"))
      (node (ref "U11") (pin "5") (pinfunction "CIN1_5") (pintype "unspecified"))
    )
    (net (code "61") (name "Net-(U11-CIN2)") (class "Default")
      (node (ref "R16") (pin "1") (pinfunction "1_1") (pintype "unspecified"))
      (node (ref "U11") (pin "6") (pinfunction "CIN2_6") (pintype "unspecified"))
    )
    (net (code "62") (name "Net-(U11-CIN3)") (class "Default")
      (node (ref "R15") (pin "1") (pinfunction "1_1") (pintype "unspecified"))
      (node (ref "U11") (pin "7") (pinfunction "CIN3_7") (pintype "unspecified"))
    )
    (net (code "63") (name "Net-(U11-CMOD)") (class "Default")
      (node (ref "U10") (pin "2") (pinfunction "2_2") (pintype "unspecified"))
      (node (ref "U11") (pin "2") (pinfunction "CMOD_2") (pintype "unspecified"))
    )
    (net (code "64") (name "Net-(U11-OUT0)") (class "Default")
      (node (ref "R34") (pin "2") (pinfunction "2_2") (pintype "unspecified"))
      (node (ref "U11") (pin "13") (pinfunction "OUT0_13") (pintype "unspecified"))
      (node (ref "U2") (pin "3") (pinfunction "E_3") (pintype "unspecified"))
    )
    (net (code "65") (name "Net-(U11-OUT1)") (class "Default")
      (node (ref "R33") (pin "2") (pinfunction "2_2") (pintype "unspecified"))
      (node (ref "U11") (pin "12") (pinfunction "OUT1_12") (pintype "unspecified"))
      (node (ref "U2") (pin "4") (pinfunction "F_4") (pintype "unspecified"))
    )
    (net (code "66") (name "Net-(U11-OUT2)") (class "Default")
      (node (ref "R30") (pin "2") (pinfunction "2_2") (pintype "unspecified"))
      (node (ref "U11") (pin "11") (pinfunction "OUT2_11") (pintype "unspecified"))
      (node (ref "U2") (pin "5") (pinfunction "G_5") (pintype "unspecified"))
    )
    (net (code "67") (name "Net-(U11-OUT3)") (class "Default")
      (node (ref "R29") (pin "2") (pinfunction "2_2") (pintype "unspecified"))
      (node (ref "U11") (pin "10") (pinfunction "OUT3_10") (pintype "unspecified"))
      (node (ref "U2") (pin "6") (pinfunction "H_6") (pintype "unspecified"))
    )
    (net (code "68") (name "Net-(U13-CDC)") (class "Default")
      (node (ref "C6") (pin "1") (pinfunction "1_1") (pintype "unspecified"))
      (node (ref "U13") (pin "3") (pinfunction "CDC_3") (pintype "unspecified"))
    )
    (net (code "69") (name "Net-(U13-CIN0)") (class "Default")
      (node (ref "R14") (pin "1") (pinfunction "1_1") (pintype "unspecified"))
      (node (ref "U13") (pin "4") (pinfunction "CIN0_4") (pintype "unspecified"))
    )
    (net (code "70") (name "Net-(U13-CIN1)") (class "Default")
      (node (ref "R13") (pin "1") (pinfunction "1_1") (pintype "unspecified"))
      (node (ref "U13") (pin "5") (pinfunction "CIN1_5") (pintype "unspecified"))
    )
    (net (code "71") (name "Net-(U13-CIN2)") (class "Default")
      (node (ref "R12") (pin "1") (pinfunction "1_1") (pintype "unspecified"))
      (node (ref "U13") (pin "6") (pinfunction "CIN2_6") (pintype "unspecified"))
    )
    (net (code "72") (name "Net-(U13-CIN3)") (class "Default")
      (node (ref "R11") (pin "1") (pinfunction "1_1") (pintype "unspecified"))
      (node (ref "U13") (pin "7") (pinfunction "CIN3_7") (pintype "unspecified"))
    )
    (net (code "73") (name "Net-(U13-CMOD)") (class "Default")
      (node (ref "U12") (pin "2") (pinfunction "2_2") (pintype "unspecified"))
      (node (ref "U13") (pin "2") (pinfunction "CMOD_2") (pintype "unspecified"))
    )
    (net (code "74") (name "Net-(U13-OUT0)") (class "Default")
      (node (ref "R38") (pin "2") (pinfunction "2_2") (pintype "unspecified"))
      (node (ref "U13") (pin "13") (pinfunction "OUT0_13") (pintype "unspecified"))
      (node (ref "U7") (pin "11") (pinfunction "A_11") (pintype "unspecified"))
    )
    (net (code "75") (name "Net-(U13-OUT1)") (class "Default")
      (node (ref "R37") (pin "2") (pinfunction "2_2") (pintype "unspecified"))
      (node (ref "U13") (pin "12") (pinfunction "OUT1_12") (pintype "unspecified"))
      (node (ref "U7") (pin "12") (pinfunction "B_12") (pintype "unspecified"))
    )
    (net (code "76") (name "Net-(U13-OUT2)") (class "Default")
      (node (ref "R36") (pin "2") (pinfunction "2_2") (pintype "unspecified"))
      (node (ref "U13") (pin "11") (pinfunction "OUT2_11") (pintype "unspecified"))
      (node (ref "U7") (pin "13") (pinfunction "C_13") (pintype "unspecified"))
    )
    (net (code "77") (name "Net-(U13-OUT3)") (class "Default")
      (node (ref "R35") (pin "2") (pinfunction "2_2") (pintype "unspecified"))
      (node (ref "U13") (pin "10") (pinfunction "OUT3_10") (pintype "unspecified"))
      (node (ref "U7") (pin "14") (pinfunction "D_14") (pintype "unspecified"))
    )
    (net (code "78") (name "Net-(U15-CDC)") (class "Default")
      (node (ref "C7") (pin "1") (pinfunction "1_1") (pintype "unspecified"))
      (node (ref "U15") (pin "3") (pinfunction "CDC_3") (pintype "unspecified"))
    )
    (net (code "79") (name "Net-(U15-CIN0)") (class "Default")
      (node (ref "R10") (pin "1") (pinfunction "1_1") (pintype "unspecified"))
      (node (ref "U15") (pin "4") (pinfunction "CIN0_4") (pintype "unspecified"))
    )
    (net (code "80") (name "Net-(U15-CIN1)") (class "Default")
      (node (ref "R9") (pin "1") (pinfunction "1_1") (pintype "unspecified"))
      (node (ref "U15") (pin "5") (pinfunction "CIN1_5") (pintype "unspecified"))
    )
    (net (code "81") (name "Net-(U15-CIN2)") (class "Default")
      (node (ref "R8") (pin "1") (pinfunction "1_1") (pintype "unspecified"))
      (node (ref "U15") (pin "6") (pinfunction "CIN2_6") (pintype "unspecified"))
    )
    (net (code "82") (name "Net-(U15-CIN3)") (class "Default")
      (node (ref "R5") (pin "1") (pinfunction "1_1") (pintype "unspecified"))
      (node (ref "U15") (pin "7") (pinfunction "CIN3_7") (pintype "unspecified"))
    )
    (net (code "83") (name "Net-(U15-CMOD)") (class "Default")
      (node (ref "U14") (pin "2") (pinfunction "2_2") (pintype "unspecified"))
      (node (ref "U15") (pin "2") (pinfunction "CMOD_2") (pintype "unspecified"))
    )
    (net (code "84") (name "Net-(U15-OUT0)") (class "Default")
      (node (ref "R43") (pin "2") (pinfunction "2_2") (pintype "unspecified"))
      (node (ref "U15") (pin "13") (pinfunction "OUT0_13") (pintype "unspecified"))
      (node (ref "U7") (pin "3") (pinfunction "E_3") (pintype "unspecified"))
    )
    (net (code "85") (name "Net-(U15-OUT1)") (class "Default")
      (node (ref "R42") (pin "2") (pinfunction "2_2") (pintype "unspecified"))
      (node (ref "U15") (pin "12") (pinfunction "OUT1_12") (pintype "unspecified"))
      (node (ref "U7") (pin "4") (pinfunction "F_4") (pintype "unspecified"))
    )
    (net (code "86") (name "Net-(U15-OUT2)") (class "Default")
      (node (ref "R40") (pin "2") (pinfunction "2_2") (pintype "unspecified"))
      (node (ref "U15") (pin "11") (pinfunction "OUT2_11") (pintype "unspecified"))
      (node (ref "U7") (pin "5") (pinfunction "G_5") (pintype "unspecified"))
    )
    (net (code "87") (name "Net-(U15-OUT3)") (class "Default")
      (node (ref "R39") (pin "2") (pinfunction "2_2") (pintype "unspecified"))
      (node (ref "U15") (pin "10") (pinfunction "OUT3_10") (pintype "unspecified"))
      (node (ref "U7") (pin "6") (pinfunction "H_6") (pintype "unspecified"))
    )
    (net (code "88") (name "RTS") (class "Default")
      (node (ref "Q2") (pin "2") (pinfunction "E_2") (pintype "unspecified"))
      (node (ref "R6") (pin "1") (pinfunction "1_1") (pintype "input"))
      (node (ref "U4") (pin "14") (pinfunction "RTS#_14") (pintype "unspecified"))
    )
    (net (code "89") (name "RX") (class "Default")
      (node (ref "U1") (pin "38") (pinfunction "RXD0_38") (pintype "unspecified"))
      (node (ref "U4") (pin "2") (pinfunction "TXD_2") (pintype "unspecified"))
    )
    (net (code "90") (name "TX") (class "Default")
      (node (ref "U1") (pin "37") (pinfunction "TXD0_37") (pintype "unspecified"))
      (node (ref "U4") (pin "3") (pinfunction "RXD_3") (pintype "unspecified"))
    )
    (net (code "91") (name "U+") (class "Default")
      (node (ref "U1") (pin "23") (pinfunction "IO20_23") (pintype "unspecified"))
      (node (ref "USB3") (pin "A6") (pinfunction "DP1_A6") (pintype "unspecified"))
      (node (ref "USB3") (pin "B6") (pinfunction "DP2_B6") (pintype "unspecified"))
    )
    (net (code "92") (name "U-") (class "Default")
      (node (ref "U1") (pin "22") (pinfunction "IO19_22") (pintype "unspecified"))
      (node (ref "USB3") (pin "A7") (pinfunction "DN1_A7") (pintype "unspecified"))
      (node (ref "USB3") (pin "B7") (pinfunction "DN2_B7") (pintype "unspecified"))
    )
    (net (code "93") (name "VBUS") (class "Default")
      (node (ref "C14") (pin "1") (pinfunction "1_1") (pintype "unspecified"))
      (node (ref "U16") (pin "1") (pinfunction "Vin_1") (pintype "unspecified"))
      (node (ref "USB2") (pin "A4B9") (pinfunction "VBUS_A4B9") (pintype "unspecified"))
      (node (ref "USB2") (pin "B4A9") (pinfunction "VBUS_B4A9") (pintype "unspecified"))
      (node (ref "USB3") (pin "A4B9") (pinfunction "VBUS_A4B9") (pintype "unspecified"))
      (node (ref "USB3") (pin "B4A9") (pinfunction "VBUS_B4A9") (pintype "unspecified"))
    )
    (net (code "94") (name "VCC") (class "Default")
      (node (ref "C15") (pin "1") (pinfunction "1_1") (pintype "input"))
      (node (ref "CN1") (pin "4") (pinfunction "4_4") (pintype "unspecified"))
      (node (ref "H1") (pin "1") (pinfunction "1_1") (pintype "input"))
      (node (ref "L1") (pin "1") (pinfunction "1_1") (pintype "unspecified"))
      (node (ref "LED1") (pin "1") (pinfunction "1_1") (pintype "unspecified"))
      (node (ref "LED10") (pin "1") (pinfunction "VDD_1") (pintype "unspecified"))
      (node (ref "LED11") (pin "1") (pinfunction "VDD_1") (pintype "unspecified"))
      (node (ref "LED12") (pin "1") (pinfunction "VDD_1") (pintype "unspecified"))
      (node (ref "LED13") (pin "1") (pinfunction "VDD_1") (pintype "unspecified"))
      (node (ref "LED14") (pin "1") (pinfunction "VDD_1") (pintype "unspecified"))
      (node (ref "LED15") (pin "1") (pinfunction "VDD_1") (pintype "unspecified"))
      (node (ref "LED16") (pin "1") (pinfunction "VDD_1") (pintype "unspecified"))
      (node (ref "LED17") (pin "1") (pinfunction "VDD_1") (pintype "unspecified"))
      (node (ref "LED2") (pin "1") (pinfunction "VDD_1") (pintype "unspecified"))
      (node (ref "LED3") (pin "1") (pinfunction "VDD_1") (pintype "unspecified"))
      (node (ref "LED4") (pin "1") (pinfunction "VDD_1") (pintype "unspecified"))
      (node (ref "LED5") (pin "1") (pinfunction "VDD_1") (pintype "unspecified"))
      (node (ref "LED6") (pin "1") (pinfunction "VDD_1") (pintype "unspecified"))
      (node (ref "LED7") (pin "1") (pinfunction "VDD_1") (pintype "unspecified"))
      (node (ref "LED8") (pin "1") (pinfunction "VDD_1") (pintype "unspecified"))
      (node (ref "LED9") (pin "1") (pinfunction "VDD_1") (pintype "unspecified"))
      (node (ref "R1") (pin "1") (pinfunction "1_1") (pintype "unspecified"))
      (node (ref "R25") (pin "1") (pinfunction "1_1") (pintype "unspecified"))
      (node (ref "R26") (pin "1") (pinfunction "1_1") (pintype "unspecified"))
      (node (ref "R27") (pin "1") (pinfunction "1_1") (pintype "unspecified"))
      (node (ref "R28") (pin "1") (pinfunction "1_1") (pintype "unspecified"))
      (node (ref "R29") (pin "1") (pinfunction "1_1") (pintype "unspecified"))
      (node (ref "R30") (pin "1") (pinfunction "1_1") (pintype "unspecified"))
      (node (ref "R31") (pin "3") (pinfunction "3_3") (pintype "input"))
      (node (ref "R32") (pin "3") (pinfunction "3_3") (pintype "input"))
      (node (ref "R33") (pin "1") (pinfunction "1_1") (pintype "unspecified"))
      (node (ref "R34") (pin "1") (pinfunction "1_1") (pintype "unspecified"))
      (node (ref "R35") (pin "1") (pinfunction "1_1") (pintype "unspecified"))
      (node (ref "R36") (pin "1") (pinfunction "1_1") (pintype "unspecified"))
      (node (ref "R37") (pin "1") (pinfunction "1_1") (pintype "unspecified"))
      (node (ref "R38") (pin "1") (pinfunction "1_1") (pintype "unspecified"))
      (node (ref "R39") (pin "1") (pinfunction "1_1") (pintype "unspecified"))
      (node (ref "R40") (pin "1") (pinfunction "1_1") (pintype "unspecified"))
      (node (ref "R41") (pin "3") (pinfunction "3_3") (pintype "input"))
      (node (ref "R42") (pin "1") (pinfunction "1_1") (pintype "unspecified"))
      (node (ref "R43") (pin "1") (pinfunction "1_1") (pintype "unspecified"))
      (node (ref "U1") (pin "2") (pinfunction "3V3_2") (pintype "unspecified"))
      (node (ref "U11") (pin "15") (pinfunction "MD_15") (pintype "unspecified"))
      (node (ref "U11") (pin "16") (pinfunction "VDD_16") (pintype "unspecified"))
      (node (ref "U13") (pin "15") (pinfunction "MD_15") (pintype "unspecified"))
      (node (ref "U13") (pin "16") (pinfunction "VDD_16") (pintype "unspecified"))
      (node (ref "U15") (pin "15") (pinfunction "MD_15") (pintype "unspecified"))
      (node (ref "U15") (pin "16") (pinfunction "VDD_16") (pintype "unspecified"))
      (node (ref "U16") (pin "4") (pinfunction "Feedback_4") (pintype "unspecified"))
      (node (ref "U2") (pin "16") (pinfunction "VCC_16") (pintype "unspecified"))
      (node (ref "U4") (pin "16") (pinfunction "VCC_16") (pintype "unspecified"))
      (node (ref "U5") (pin "1a") (pinfunction "1a_1a") (pintype "unspecified"))
      (node (ref "U5") (pin "1b") (pinfunction "1b_1b") (pintype "unspecified"))
      (node (ref "U7") (pin "16") (pinfunction "VCC_16") (pintype "unspecified"))
      (node (ref "U8") (pin "15") (pinfunction "MD_15") (pintype "unspecified"))
      (node (ref "U8") (pin "16") (pinfunction "VDD_16") (pintype "unspecified"))
      (node (ref "U9") (pin "2") (pinfunction "2_2") (pintype "unspecified"))
    )
    (net (code "95") (name "unconnected-(LED17-DOUT-Pad2)") (class "Default")
      (node (ref "LED17") (pin "2") (pinfunction "DOUT_2") (pintype "unspecified"))
    )
    (net (code "96") (name "unconnected-(R5-Pad2)") (class "Default")
      (node (ref "R5") (pin "2") (pinfunction "2_2") (pintype "unspecified"))
    )
    (net (code "97") (name "unconnected-(R8-Pad2)") (class "Default")
      (node (ref "R8") (pin "2") (pinfunction "2_2") (pintype "unspecified"))
    )
    (net (code "98") (name "unconnected-(R9-Pad2)") (class "Default")
      (node (ref "R9") (pin "2") (pinfunction "2_2") (pintype "unspecified"))
    )
    (net (code "99") (name "unconnected-(R10-Pad2)") (class "Default")
      (node (ref "R10") (pin "2") (pinfunction "2_2") (pintype "unspecified"))
    )
    (net (code "100") (name "unconnected-(R11-Pad2)") (class "Default")
      (node (ref "R11") (pin "2") (pinfunction "2_2") (pintype "unspecified"))
    )
    (net (code "101") (name "unconnected-(R12-Pad2)") (class "Default")
      (node (ref "R12") (pin "2") (pinfunction "2_2") (pintype "unspecified"))
    )
    (net (code "102") (name "unconnected-(R13-Pad2)") (class "Default")
      (node (ref "R13") (pin "2") (pinfunction "2_2") (pintype "unspecified"))
    )
    (net (code "103") (name "unconnected-(R14-Pad2)") (class "Default")
      (node (ref "R14") (pin "2") (pinfunction "2_2") (pintype "unspecified"))
    )
    (net (code "104") (name "unconnected-(R15-Pad2)") (class "Default")
      (node (ref "R15") (pin "2") (pinfunction "2_2") (pintype "unspecified"))
    )
    (net (code "105") (name "unconnected-(R16-Pad2)") (class "Default")
      (node (ref "R16") (pin "2") (pinfunction "2_2") (pintype "unspecified"))
    )
    (net (code "106") (name "unconnected-(R17-Pad2)") (class "Default")
      (node (ref "R17") (pin "2") (pinfunction "2_2") (pintype "unspecified"))
    )
    (net (code "107") (name "unconnected-(R18-Pad2)") (class "Default")
      (node (ref "R18") (pin "2") (pinfunction "2_2") (pintype "unspecified"))
    )
    (net (code "108") (name "unconnected-(R19-Pad2)") (class "Default")
      (node (ref "R19") (pin "2") (pinfunction "2_2") (pintype "unspecified"))
    )
    (net (code "109") (name "unconnected-(R20-Pad2)") (class "Default")
      (node (ref "R20") (pin "2") (pinfunction "2_2") (pintype "unspecified"))
    )
    (net (code "110") (name "unconnected-(R21-Pad2)") (class "Default")
      (node (ref "R21") (pin "2") (pinfunction "2_2") (pintype "unspecified"))
    )
    (net (code "111") (name "unconnected-(R22-Pad2)") (class "Default")
      (node (ref "R22") (pin "2") (pinfunction "2_2") (pintype "unspecified"))
    )
    (net (code "112") (name "unconnected-(U1-IO1-Pad4)") (class "Default")
      (node (ref "U1") (pin "4") (pinfunction "IO1_4") (pintype "unspecified"))
    )
    (net (code "113") (name "unconnected-(U1-IO2-Pad5)") (class "Default")
      (node (ref "U1") (pin "5") (pinfunction "IO2_5") (pintype "unspecified"))
    )
    (net (code "114") (name "unconnected-(U1-IO3-Pad6)") (class "Default")
      (node (ref "U1") (pin "6") (pinfunction "IO3_6") (pintype "unspecified"))
    )
    (net (code "115") (name "unconnected-(U1-IO4-Pad7)") (class "Default")
      (node (ref "U1") (pin "7") (pinfunction "IO4_7") (pintype "unspecified"))
    )
    (net (code "116") (name "unconnected-(U1-IO5-Pad8)") (class "Default")
      (node (ref "U1") (pin "8") (pinfunction "IO5_8") (pintype "unspecified"))
    )
    (net (code "117") (name "unconnected-(U1-IO37-Pad31)") (class "Default")
      (node (ref "U1") (pin "31") (pinfunction "IO37_31") (pintype "unspecified"))
    )
    (net (code "118") (name "unconnected-(U1-IO38-Pad32)") (class "Default")
      (node (ref "U1") (pin "32") (pinfunction "IO38_32") (pintype "unspecified"))
    )
    (net (code "119") (name "unconnected-(U1-IO39-Pad33)") (class "Default")
      (node (ref "U1") (pin "33") (pinfunction "IO39_33") (pintype "unspecified"))
    )
    (net (code "120") (name "unconnected-(U1-IO40-Pad34)") (class "Default")
      (node (ref "U1") (pin "34") (pinfunction "IO40_34") (pintype "unspecified"))
    )
    (net (code "121") (name "unconnected-(U1-IO41-Pad35)") (class "Default")
      (node (ref "U1") (pin "35") (pinfunction "IO41_35") (pintype "unspecified"))
    )
    (net (code "122") (name "unconnected-(U1-IO42-Pad36)") (class "Default")
      (node (ref "U1") (pin "36") (pinfunction "IO42_36") (pintype "unspecified"))
    )
    (net (code "123") (name "unconnected-(U1-IO45-Pad39)") (class "Default")
      (node (ref "U1") (pin "39") (pinfunction "IO45_39") (pintype "unspecified"))
    )
    (net (code "124") (name "unconnected-(U1-IO46-Pad40)") (class "Default")
      (node (ref "U1") (pin "40") (pinfunction "IO46_40") (pintype "unspecified"))
    )
    (net (code "125") (name "unconnected-(U2-QH#-Pad7)") (class "Default")
      (node (ref "U2") (pin "7") (pinfunction "QH#_7") (pintype "unspecified"))
    )
    (net (code "126") (name "unconnected-(U2-SER-Pad10)") (class "Default")
      (node (ref "U2") (pin "10") (pinfunction "SER_10") (pintype "unspecified"))
    )
    (net (code "127") (name "unconnected-(U4-CTS#-Pad9)") (class "Default")
      (node (ref "U4") (pin "9") (pinfunction "CTS#_9") (pintype "unspecified+no_connect"))
    )
    (net (code "128") (name "unconnected-(U4-DCD#-Pad12)") (class "Default")
      (node (ref "U4") (pin "12") (pinfunction "DCD#_12") (pintype "unspecified+no_connect"))
    )
    (net (code "129") (name "unconnected-(U4-DSR#-Pad10)") (class "Default")
      (node (ref "U4") (pin "10") (pinfunction "DSR#_10") (pintype "unspecified+no_connect"))
    )
    (net (code "130") (name "unconnected-(U4-NC.-Pad7)") (class "Default")
      (node (ref "U4") (pin "7") (pinfunction "NC._7") (pintype "unspecified+no_connect"))
    )
    (net (code "131") (name "unconnected-(U4-OUT#-Pad8)") (class "Default")
      (node (ref "U4") (pin "8") (pinfunction "OUT#_8") (pintype "unspecified+no_connect"))
    )
    (net (code "132") (name "unconnected-(U4-R232-Pad15)") (class "Default")
      (node (ref "U4") (pin "15") (pinfunction "R232_15") (pintype "unspecified+no_connect"))
    )
    (net (code "133") (name "unconnected-(U4-RI#-Pad11)") (class "Default")
      (node (ref "U4") (pin "11") (pinfunction "RI#_11") (pintype "unspecified+no_connect"))
    )
    (net (code "134") (name "unconnected-(U7-QH-Pad9)") (class "Default")
      (node (ref "U7") (pin "9") (pinfunction "QH_9") (pintype "unspecified"))
    )
    (net (code "135") (name "unconnected-(U8-NC-Pad8)") (class "Default")
      (node (ref "U8") (pin "8") (pinfunction "NC_8") (pintype "unspecified+no_connect"))
    )
    (net (code "136") (name "unconnected-(U8-NC-Pad9)") (class "Default")
      (node (ref "U8") (pin "9") (pinfunction "NC_9") (pintype "unspecified+no_connect"))
    )
    (net (code "137") (name "unconnected-(U11-NC-Pad8)") (class "Default")
      (node (ref "U11") (pin "8") (pinfunction "NC_8") (pintype "unspecified+no_connect"))
    )
    (net (code "138") (name "unconnected-(U11-NC-Pad9)") (class "Default")
      (node (ref "U11") (pin "9") (pinfunction "NC_9") (pintype "unspecified+no_connect"))
    )
    (net (code "139") (name "unconnected-(U13-NC-Pad8)") (class "Default")
      (node (ref "U13") (pin "8") (pinfunction "NC_8") (pintype "unspecified+no_connect"))
    )
    (net (code "140") (name "unconnected-(U13-NC-Pad9)") (class "Default")
      (node (ref "U13") (pin "9") (pinfunction "NC_9") (pintype "unspecified+no_connect"))
    )
    (net (code "141") (name "unconnected-(U15-NC-Pad8)") (class "Default")
      (node (ref "U15") (pin "8") (pinfunction "NC_8") (pintype "unspecified+no_connect"))
    )
    (net (code "142") (name "unconnected-(U15-NC-Pad9)") (class "Default")
      (node (ref "U15") (pin "9") (pinfunction "NC_9") (pintype "unspecified+no_connect"))
    )
    (net (code "143") (name "unconnected-(USB2-CC1-PadA5)") (class "Default")
      (node (ref "USB2") (pin "A5") (pinfunction "CC1_A5") (pintype "unspecified+no_connect"))
    )
    (net (code "144") (name "unconnected-(USB2-CC2-PadB5)") (class "Default")
      (node (ref "USB2") (pin "B5") (pinfunction "CC2_B5") (pintype "unspecified+no_connect"))
    )
    (net (code "145") (name "unconnected-(USB2-SBU1-PadA8)") (class "Default")
      (node (ref "USB2") (pin "A8") (pinfunction "SBU1_A8") (pintype "unspecified+no_connect"))
    )
    (net (code "146") (name "unconnected-(USB2-SBU2-PadB8)") (class "Default")
      (node (ref "USB2") (pin "B8") (pinfunction "SBU2_B8") (pintype "unspecified+no_connect"))
    )
    (net (code "147") (name "unconnected-(USB2-SHELL-Pad1)") (class "Default")
      (node (ref "USB2") (pin "1") (pinfunction "SHELL_1") (pintype "unspecified+no_connect"))
    )
    (net (code "148") (name "unconnected-(USB2-SHELL-Pad2)") (class "Default")
      (node (ref "USB2") (pin "2") (pinfunction "SHELL_2") (pintype "unspecified+no_connect"))
    )
    (net (code "149") (name "unconnected-(USB2-SHELL-Pad3)") (class "Default")
      (node (ref "USB2") (pin "3") (pinfunction "SHELL_3") (pintype "unspecified+no_connect"))
    )
    (net (code "150") (name "unconnected-(USB2-SHELL-Pad4)") (class "Default")
      (node (ref "USB2") (pin "4") (pinfunction "SHELL_4") (pintype "unspecified+no_connect"))
    )
    (net (code "151") (name "unconnected-(USB3-CC1-PadA5)") (class "Default")
      (node (ref "USB3") (pin "A5") (pinfunction "CC1_A5") (pintype "unspecified+no_connect"))
    )
    (net (code "152") (name "unconnected-(USB3-CC2-PadB5)") (class "Default")
      (node (ref "USB3") (pin "B5") (pinfunction "CC2_B5") (pintype "unspecified+no_connect"))
    )
    (net (code "153") (name "unconnected-(USB3-SBU1-PadA8)") (class "Default")
      (node (ref "USB3") (pin "A8") (pinfunction "SBU1_A8") (pintype "unspecified+no_connect"))
    )
    (net (code "154") (name "unconnected-(USB3-SBU2-PadB8)") (class "Default")
      (node (ref "USB3") (pin "B8") (pinfunction "SBU2_B8") (pintype "unspecified+no_connect"))
    )
    (net (code "155") (name "unconnected-(USB3-SHELL-Pad1)") (class "Default")
      (node (ref "USB3") (pin "1") (pinfunction "SHELL_1") (pintype "unspecified+no_connect"))
    )
    (net (code "156") (name "unconnected-(USB3-SHELL-Pad2)") (class "Default")
      (node (ref "USB3") (pin "2") (pinfunction "SHELL_2") (pintype "unspecified+no_connect"))
    )
    (net (code "157") (name "unconnected-(USB3-SHELL-Pad3)") (class "Default")
      (node (ref "USB3") (pin "3") (pinfunction "SHELL_3") (pintype "unspecified+no_connect"))
    )
    (net (code "158") (name "unconnected-(USB3-SHELL-Pad4)") (class "Default")
      (node (ref "USB3") (pin "4") (pinfunction "SHELL_4") (pintype "unspecified+no_connect"))
    )
  )
)
